# ORCA_Logic_Circuit_Pro.net
KiCad netlist of a schematic drawn in EasyEDA Pro
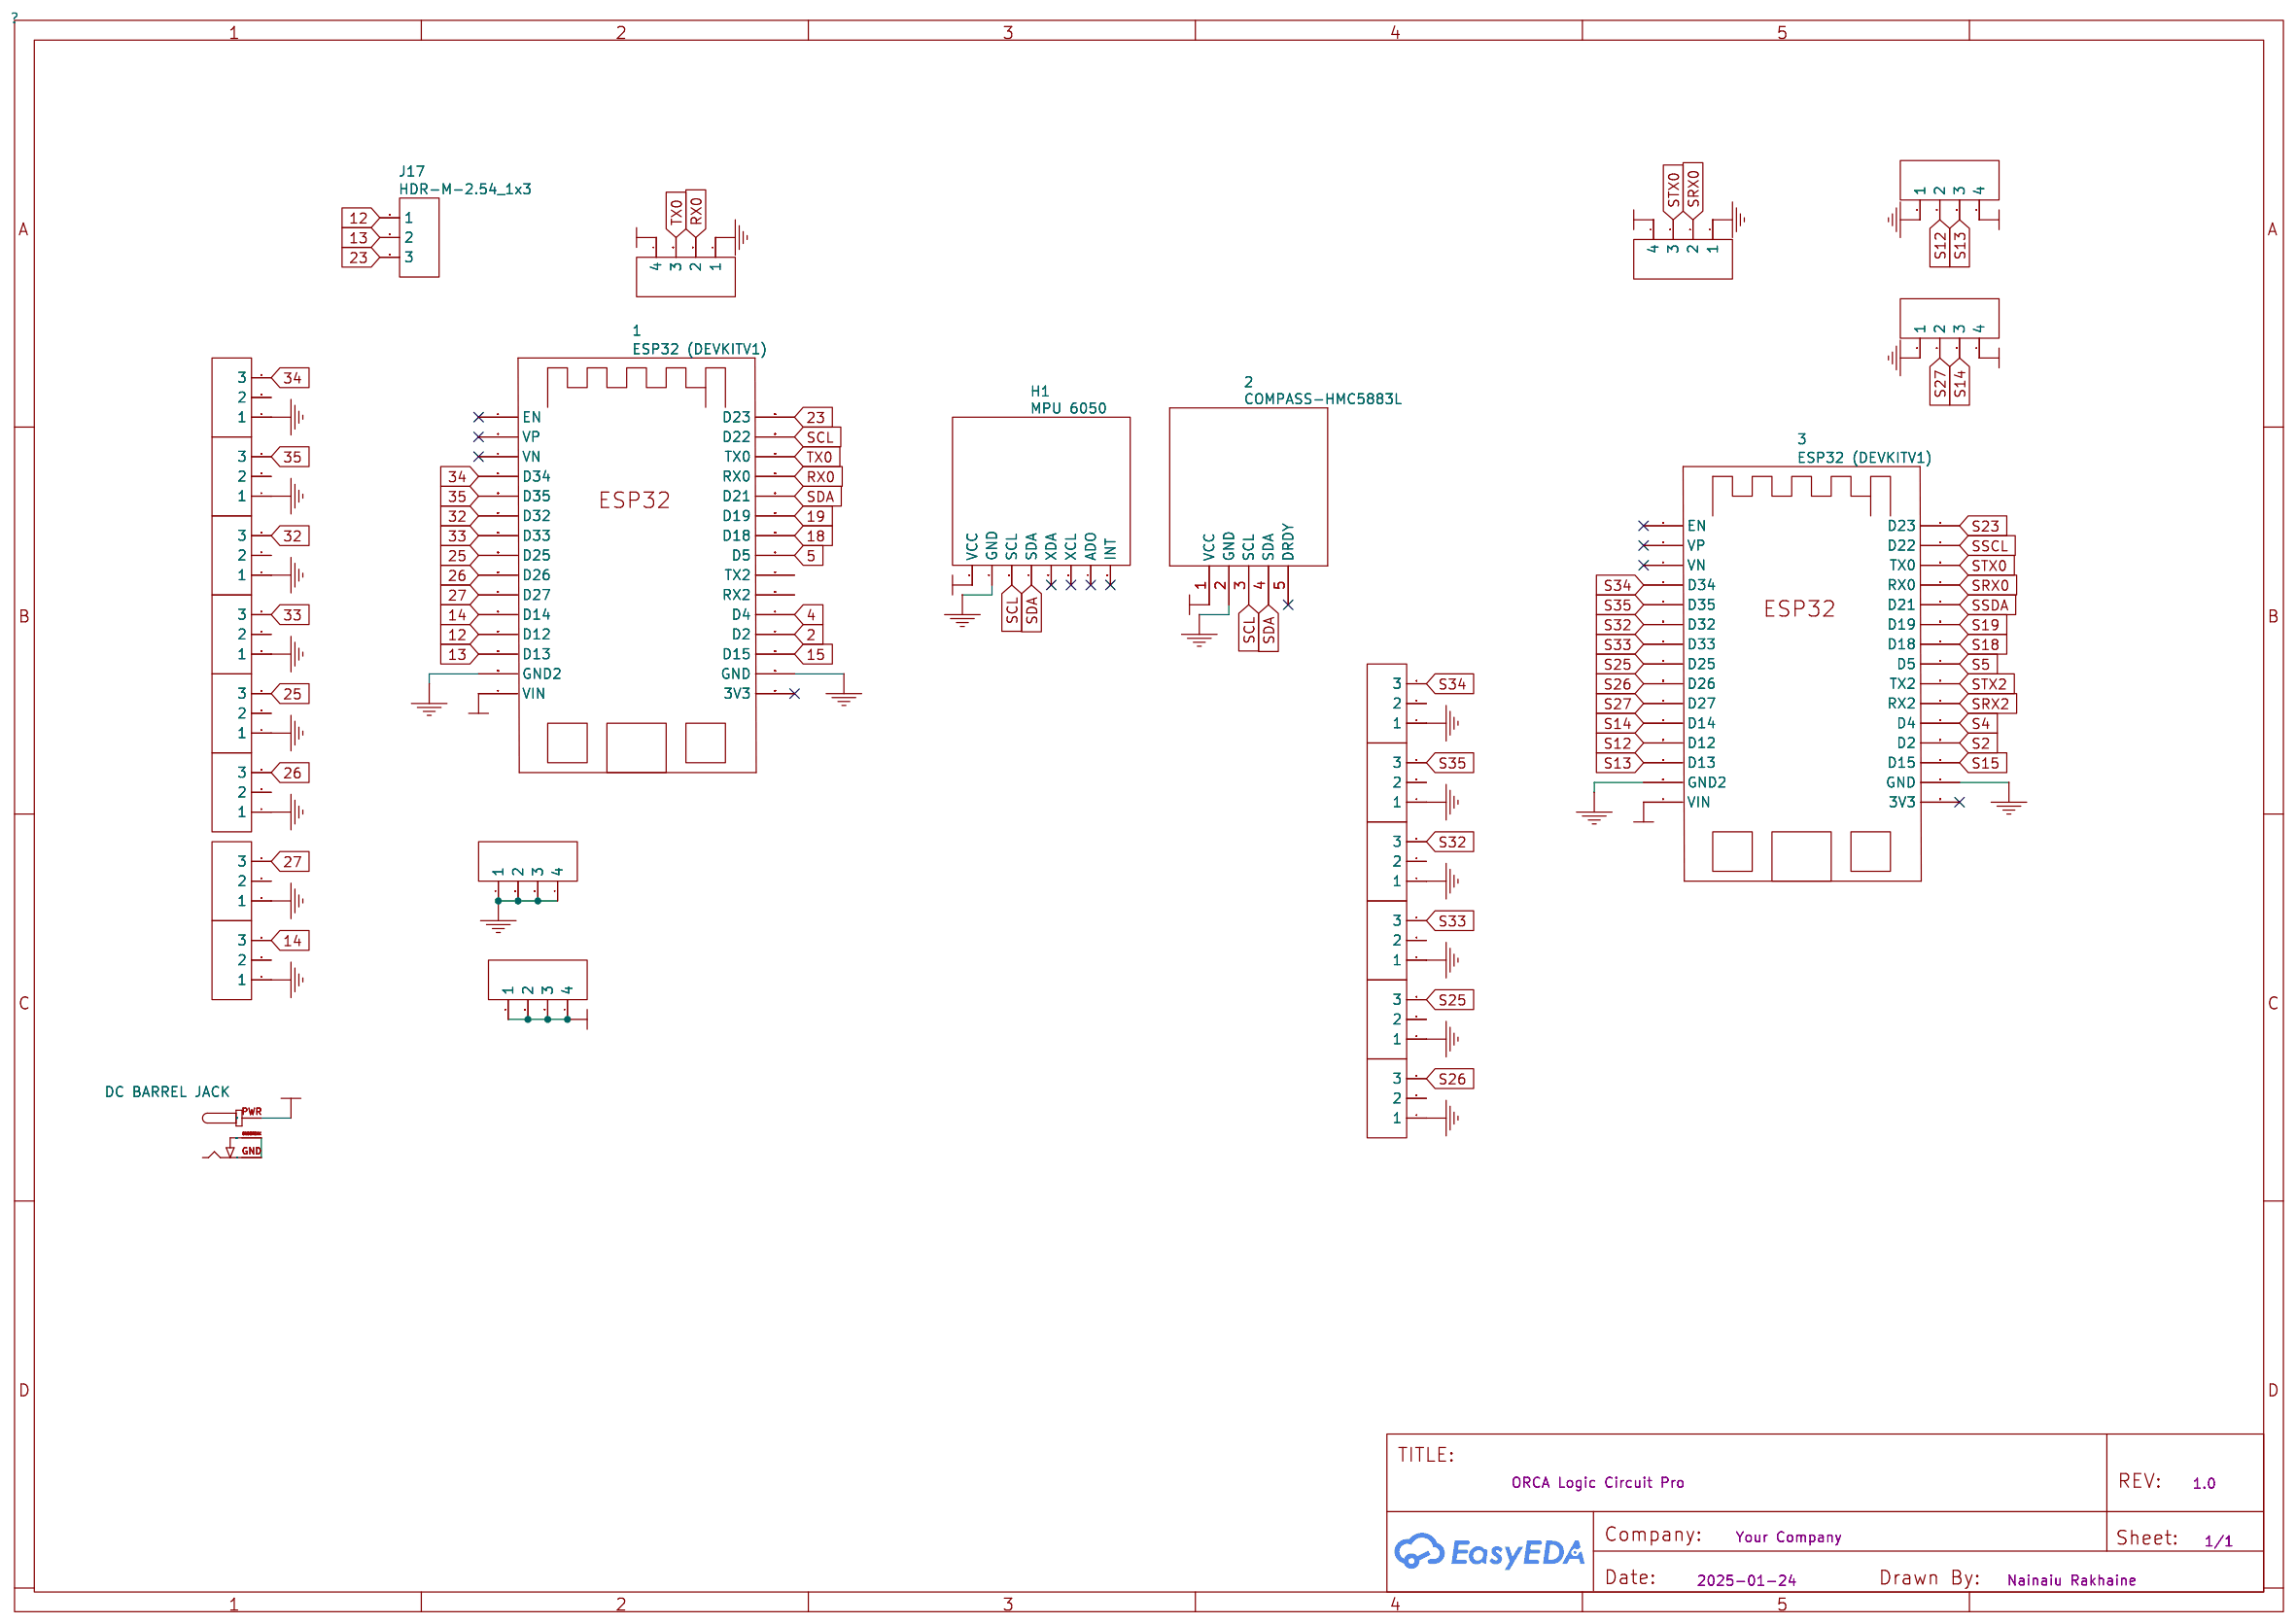
[diagram p0: schematic sheet]

(export (version "E")
  (design (tool "Eeschema 10.0.6"))
  (components
    (comp (ref "1")
      (value "ESP32 (DEVKITV1)")
      (footprint "easyedapro:ESP32-DEVKIT1")
      (libsource (lib "easyedapro") (part "ESP32 (DEVKITV1)"))
    )
    (comp (ref "2")
      (value "COMPASS-HMC5883L")
      (footprint "easyedapro:COMPASS-HMC5883L")
      (libsource (lib "easyedapro") (part "COMPASS-HMC5883L"))
    )
    (comp (ref "3")
      (value "ESP32 (DEVKITV1)")
      (footprint "easyedapro:ESP32-DEVKIT1")
      (libsource (lib "easyedapro") (part "ESP32 (DEVKITV1)"))
    )
    (comp (ref "H1")
      (value "MPU 6050")
      (footprint "easyedapro:MPU6050")
      (libsource (lib "easyedapro") (part "MPU 6050"))
    )
    (comp (ref "J1")
      (value "HDR-M-2.54_1x4")
      (footprint "easyedapro:HDR-M-2.54_1X4")
      (libsource (lib "easyedapro") (part "HDR-M-2.54_1x4"))
    )
    (comp (ref "J2")
      (value "HDR-M-2.54_1x4")
      (footprint "easyedapro:HDR-M-2.54_1X4")
      (libsource (lib "easyedapro") (part "HDR-M-2.54_1x4"))
    )
    (comp (ref "J3")
      (value "HDR-M-2.54_1x3")
      (footprint "easyedapro:HDR-M-2.54_1X3")
      (libsource (lib "") (part "HDR-M-2.54_1x3_1"))
    )
    (comp (ref "J4")
      (value "HDR-M-2.54_1x3")
      (footprint "easyedapro:HDR-M-2.54_1X3")
      (libsource (lib "") (part "HDR-M-2.54_1x3_1"))
    )
    (comp (ref "J5")
      (value "HDR-M-2.54_1x3")
      (footprint "easyedapro:HDR-M-2.54_1X3")
      (libsource (lib "") (part "HDR-M-2.54_1x3_1"))
    )
    (comp (ref "J6")
      (value "HDR-M-2.54_1x3")
      (footprint "easyedapro:HDR-M-2.54_1X3")
      (libsource (lib "") (part "HDR-M-2.54_1x3_1"))
    )
    (comp (ref "J7")
      (value "HDR-M-2.54_1x3")
      (footprint "easyedapro:HDR-M-2.54_1X3")
      (libsource (lib "") (part "HDR-M-2.54_1x3_1"))
    )
    (comp (ref "J8")
      (value "HDR-M-2.54_1x3")
      (footprint "easyedapro:HDR-M-2.54_1X3")
      (libsource (lib "") (part "HDR-M-2.54_1x3_1"))
    )
    (comp (ref "J9")
      (value "HDR-M-2.54_1x3")
      (footprint "easyedapro:HDR-M-2.54_1X3")
      (libsource (lib "") (part "HDR-M-2.54_1x3_1"))
    )
    (comp (ref "J10")
      (value "HDR-M-2.54_1x3")
      (footprint "easyedapro:HDR-M-2.54_1X3")
      (libsource (lib "") (part "HDR-M-2.54_1x3_1"))
    )
    (comp (ref "J11")
      (value "HDR-M-2.54_1x3")
      (footprint "easyedapro:HDR-M-2.54_1X3")
      (libsource (lib "") (part "HDR-M-2.54_1x3_1"))
    )
    (comp (ref "J12")
      (value "HDR-M-2.54_1x3")
      (footprint "easyedapro:HDR-M-2.54_1X3")
      (libsource (lib "") (part "HDR-M-2.54_1x3_1"))
    )
    (comp (ref "J13")
      (value "HDR-M-2.54_1x3")
      (footprint "easyedapro:HDR-M-2.54_1X3")
      (libsource (lib "") (part "HDR-M-2.54_1x3_1"))
    )
    (comp (ref "J14")
      (value "HDR-M-2.54_1x3")
      (footprint "easyedapro:HDR-M-2.54_1X3")
      (libsource (lib "") (part "HDR-M-2.54_1x3_1"))
    )
    (comp (ref "J15")
      (value "HDR-M-2.54_1x4")
      (footprint "easyedapro:HDR-M-2.54_1X4")
      (libsource (lib "easyedapro") (part "HDR-M-2.54_1x4"))
    )
    (comp (ref "J16")
      (value "HDR-M-2.54_1x4")
      (footprint "easyedapro:HDR-M-2.54_1X4")
      (libsource (lib "") (part "HDR-M-2.54_1x4_1"))
    )
    (comp (ref "J17")
      (value "HDR-M-2.54_1x3")
      (footprint "easyedapro:HDR-M-2.54_1X3")
      (libsource (lib "easyedapro") (part "HDR-M-2.54_1x3"))
    )
    (comp (ref "J18")
      (value "HDR-M-2.54_1x4")
      (footprint "easyedapro:HDR-M-2.54_1X4")
      (libsource (lib "") (part "HDR-M-2.54_1x4_1"))
    )
    (comp (ref "J19")
      (value "HDR-M-2.54_1x3")
      (footprint "easyedapro:HDR-M-2.54_1X3")
      (libsource (lib "") (part "HDR-M-2.54_1x3_1"))
    )
    (comp (ref "J21")
      (value "HDR-M-2.54_1x3")
      (footprint "easyedapro:HDR-M-2.54_1X3")
      (libsource (lib "") (part "HDR-M-2.54_1x3_1"))
    )
    (comp (ref "J22")
      (value "HDR-M-2.54_1x4")
      (footprint "easyedapro:HDR-M-2.54_1X4")
      (libsource (lib "easyedapro") (part "HDR-M-2.54_1x4"))
    )
    (comp (ref "U2")
      (value "DC BARREL JACK")
      (footprint "easyedapro:DCBARRELJACK")
      (libsource (lib "easyedapro") (part "DC BARREL JACK"))
    )
  )
  (nets
    (net (code "1") (name "+5V") (class "Default")
      (node (ref "1") (pin "VIN") (pinfunction "VIN_VIN") (pintype "unspecified"))
      (node (ref "2") (pin "1") (pinfunction "VCC_1") (pintype "bidirectional"))
      (node (ref "3") (pin "VIN") (pinfunction "VIN_VIN") (pintype "unspecified"))
      (node (ref "H1") (pin "1") (pinfunction "VCC_1") (pintype "unspecified"))
      (node (ref "J1") (pin "4") (pinfunction "4_4") (pintype "unspecified"))
      (node (ref "J15") (pin "1") (pinfunction "1_1") (pintype "unspecified"))
      (node (ref "J15") (pin "2") (pinfunction "2_2") (pintype "unspecified"))
      (node (ref "J15") (pin "3") (pinfunction "3_3") (pintype "unspecified"))
      (node (ref "J15") (pin "4") (pinfunction "4_4") (pintype "unspecified"))
      (node (ref "J16") (pin "4") (pinfunction "4_4") (pintype "unspecified"))
      (node (ref "J18") (pin "4") (pinfunction "4_4") (pintype "unspecified"))
      (node (ref "J22") (pin "4") (pinfunction "4_4") (pintype "unspecified"))
      (node (ref "U2") (pin "PWR") (pinfunction "PWR_PWR") (pintype "bidirectional"))
    )
    (net (code "2") (name "2") (class "Default")
      (node (ref "1") (pin "D2") (pinfunction "D2_D2") (pintype "unspecified"))
    )
    (net (code "3") (name "4") (class "Default")
      (node (ref "1") (pin "D4") (pinfunction "D4_D4") (pintype "unspecified"))
    )
    (net (code "4") (name "5") (class "Default")
      (node (ref "1") (pin "D5") (pinfunction "D5_D5") (pintype "unspecified"))
    )
    (net (code "5") (name "12") (class "Default")
      (node (ref "1") (pin "D12") (pinfunction "D12_D12") (pintype "unspecified"))
      (node (ref "J17") (pin "1") (pinfunction "1_1") (pintype "input"))
    )
    (net (code "6") (name "13") (class "Default")
      (node (ref "1") (pin "D13") (pinfunction "D13_D13") (pintype "unspecified"))
      (node (ref "J17") (pin "2") (pinfunction "2_2") (pintype "input"))
    )
    (net (code "7") (name "14") (class "Default")
      (node (ref "1") (pin "D14") (pinfunction "D14_D14") (pintype "unspecified"))
      (node (ref "J5") (pin "3") (pinfunction "3_3") (pintype "input"))
    )
    (net (code "8") (name "15") (class "Default")
      (node (ref "1") (pin "D15") (pinfunction "D15_D15") (pintype "unspecified"))
    )
    (net (code "9") (name "18") (class "Default")
      (node (ref "1") (pin "D18") (pinfunction "D18_D18") (pintype "unspecified"))
    )
    (net (code "10") (name "19") (class "Default")
      (node (ref "1") (pin "D19") (pinfunction "D19_D19") (pintype "unspecified"))
    )
    (net (code "11") (name "23") (class "Default")
      (node (ref "1") (pin "D23") (pinfunction "D23_D23") (pintype "unspecified"))
      (node (ref "J17") (pin "3") (pinfunction "3_3") (pintype "input"))
    )
    (net (code "12") (name "25") (class "Default")
      (node (ref "1") (pin "D25") (pinfunction "D25_D25") (pintype "unspecified"))
      (node (ref "J8") (pin "3") (pinfunction "3_3") (pintype "input"))
    )
    (net (code "13") (name "26") (class "Default")
      (node (ref "1") (pin "D26") (pinfunction "D26_D26") (pintype "unspecified"))
      (node (ref "J7") (pin "3") (pinfunction "3_3") (pintype "input"))
    )
    (net (code "14") (name "27") (class "Default")
      (node (ref "1") (pin "D27") (pinfunction "D27_D27") (pintype "unspecified"))
      (node (ref "J6") (pin "3") (pinfunction "3_3") (pintype "input"))
    )
    (net (code "15") (name "32") (class "Default")
      (node (ref "1") (pin "D32") (pinfunction "D32_D32") (pintype "unspecified"))
      (node (ref "J3") (pin "3") (pinfunction "3_3") (pintype "input"))
    )
    (net (code "16") (name "33") (class "Default")
      (node (ref "1") (pin "D33") (pinfunction "D33_D33") (pintype "unspecified"))
      (node (ref "J4") (pin "3") (pinfunction "3_3") (pintype "input"))
    )
    (net (code "17") (name "34") (class "Default")
      (node (ref "1") (pin "D34") (pinfunction "D34_D34") (pintype "unspecified"))
      (node (ref "J14") (pin "3") (pinfunction "3_3") (pintype "input"))
    )
    (net (code "18") (name "35") (class "Default")
      (node (ref "1") (pin "D35") (pinfunction "D35_D35") (pintype "unspecified"))
      (node (ref "J13") (pin "3") (pinfunction "3_3") (pintype "input"))
    )
    (net (code "19") (name "GND") (class "Default")
      (node (ref "1") (pin "GND") (pinfunction "GND_GND") (pintype "unspecified"))
      (node (ref "1") (pin "GND2") (pinfunction "GND2_GND2") (pintype "unspecified"))
      (node (ref "2") (pin "2") (pinfunction "GND_2") (pintype "bidirectional"))
      (node (ref "3") (pin "GND") (pinfunction "GND_GND") (pintype "unspecified"))
      (node (ref "3") (pin "GND2") (pinfunction "GND2_GND2") (pintype "unspecified"))
      (node (ref "H1") (pin "2") (pinfunction "GND_2") (pintype "unspecified"))
      (node (ref "J1") (pin "1") (pinfunction "1_1") (pintype "unspecified"))
      (node (ref "J10") (pin "1") (pinfunction "1_1") (pintype "input"))
      (node (ref "J11") (pin "1") (pinfunction "1_1") (pintype "input"))
      (node (ref "J12") (pin "1") (pinfunction "1_1") (pintype "input"))
      (node (ref "J13") (pin "1") (pinfunction "1_1") (pintype "input"))
      (node (ref "J14") (pin "1") (pinfunction "1_1") (pintype "input"))
      (node (ref "J16") (pin "1") (pinfunction "1_1") (pintype "unspecified"))
      (node (ref "J18") (pin "1") (pinfunction "1_1") (pintype "unspecified"))
      (node (ref "J19") (pin "1") (pinfunction "1_1") (pintype "input"))
      (node (ref "J2") (pin "1") (pinfunction "1_1") (pintype "unspecified"))
      (node (ref "J2") (pin "2") (pinfunction "2_2") (pintype "unspecified"))
      (node (ref "J2") (pin "3") (pinfunction "3_3") (pintype "unspecified"))
      (node (ref "J2") (pin "4") (pinfunction "4_4") (pintype "unspecified"))
      (node (ref "J21") (pin "1") (pinfunction "1_1") (pintype "input"))
      (node (ref "J22") (pin "1") (pinfunction "1_1") (pintype "unspecified"))
      (node (ref "J3") (pin "1") (pinfunction "1_1") (pintype "input"))
      (node (ref "J4") (pin "1") (pinfunction "1_1") (pintype "input"))
      (node (ref "J5") (pin "1") (pinfunction "1_1") (pintype "input"))
      (node (ref "J6") (pin "1") (pinfunction "1_1") (pintype "input"))
      (node (ref "J7") (pin "1") (pinfunction "1_1") (pintype "input"))
      (node (ref "J8") (pin "1") (pinfunction "1_1") (pintype "input"))
      (node (ref "J9") (pin "1") (pinfunction "1_1") (pintype "input"))
    )
    (net (code "20") (name "Net-(U2-PadGND)") (class "Default")
      (node (ref "U2") (pin "GND") (pinfunction "GND_GND") (pintype "bidirectional"))
      (node (ref "U2") (pin "GNDBREAK") (pinfunction "GNDBREAK_GNDBREAK") (pintype "bidirectional"))
    )
    (net (code "21") (name "RX0") (class "Default")
      (node (ref "1") (pin "RX0") (pinfunction "RX0_RX0") (pintype "unspecified"))
      (node (ref "J16") (pin "2") (pinfunction "2_2") (pintype "unspecified"))
    )
    (net (code "22") (name "S2") (class "Default")
      (node (ref "3") (pin "D2") (pinfunction "D2_D2") (pintype "unspecified"))
    )
    (net (code "23") (name "S4") (class "Default")
      (node (ref "3") (pin "D4") (pinfunction "D4_D4") (pintype "unspecified"))
    )
    (net (code "24") (name "S5") (class "Default")
      (node (ref "3") (pin "D5") (pinfunction "D5_D5") (pintype "unspecified"))
    )
    (net (code "25") (name "S12") (class "Default")
      (node (ref "3") (pin "D12") (pinfunction "D12_D12") (pintype "unspecified"))
      (node (ref "J1") (pin "2") (pinfunction "2_2") (pintype "unspecified"))
    )
    (net (code "26") (name "S13") (class "Default")
      (node (ref "3") (pin "D13") (pinfunction "D13_D13") (pintype "unspecified"))
      (node (ref "J1") (pin "3") (pinfunction "3_3") (pintype "unspecified"))
    )
    (net (code "27") (name "S14") (class "Default")
      (node (ref "3") (pin "D14") (pinfunction "D14_D14") (pintype "unspecified"))
      (node (ref "J22") (pin "3") (pinfunction "3_3") (pintype "unspecified"))
    )
    (net (code "28") (name "S15") (class "Default")
      (node (ref "3") (pin "D15") (pinfunction "D15_D15") (pintype "unspecified"))
    )
    (net (code "29") (name "S18") (class "Default")
      (node (ref "3") (pin "D18") (pinfunction "D18_D18") (pintype "unspecified"))
    )
    (net (code "30") (name "S19") (class "Default")
      (node (ref "3") (pin "D19") (pinfunction "D19_D19") (pintype "unspecified"))
    )
    (net (code "31") (name "S23") (class "Default")
      (node (ref "3") (pin "D23") (pinfunction "D23_D23") (pintype "unspecified"))
    )
    (net (code "32") (name "S25") (class "Default")
      (node (ref "3") (pin "D25") (pinfunction "D25_D25") (pintype "unspecified"))
      (node (ref "J19") (pin "3") (pinfunction "3_3") (pintype "input"))
    )
    (net (code "33") (name "S26") (class "Default")
      (node (ref "3") (pin "D26") (pinfunction "D26_D26") (pintype "unspecified"))
      (node (ref "J21") (pin "3") (pinfunction "3_3") (pintype "input"))
    )
    (net (code "34") (name "S27") (class "Default")
      (node (ref "3") (pin "D27") (pinfunction "D27_D27") (pintype "unspecified"))
      (node (ref "J22") (pin "2") (pinfunction "2_2") (pintype "unspecified"))
    )
    (net (code "35") (name "S32") (class "Default")
      (node (ref "3") (pin "D32") (pinfunction "D32_D32") (pintype "unspecified"))
      (node (ref "J11") (pin "3") (pinfunction "3_3") (pintype "input"))
    )
    (net (code "36") (name "S33") (class "Default")
      (node (ref "3") (pin "D33") (pinfunction "D33_D33") (pintype "unspecified"))
      (node (ref "J12") (pin "3") (pinfunction "3_3") (pintype "input"))
    )
    (net (code "37") (name "S34") (class "Default")
      (node (ref "3") (pin "D34") (pinfunction "D34_D34") (pintype "unspecified"))
      (node (ref "J9") (pin "3") (pinfunction "3_3") (pintype "input"))
    )
    (net (code "38") (name "S35") (class "Default")
      (node (ref "3") (pin "D35") (pinfunction "D35_D35") (pintype "unspecified"))
      (node (ref "J10") (pin "3") (pinfunction "3_3") (pintype "input"))
    )
    (net (code "39") (name "SCL") (class "Default")
      (node (ref "1") (pin "D22") (pinfunction "D22_D22") (pintype "unspecified"))
      (node (ref "2") (pin "3") (pinfunction "SCL_3") (pintype "bidirectional"))
      (node (ref "H1") (pin "3") (pinfunction "SCL_3") (pintype "unspecified"))
    )
    (net (code "40") (name "SDA") (class "Default")
      (node (ref "1") (pin "D21") (pinfunction "D21_D21") (pintype "unspecified"))
      (node (ref "2") (pin "4") (pinfunction "SDA_4") (pintype "bidirectional"))
      (node (ref "H1") (pin "4") (pinfunction "SDA_4") (pintype "unspecified"))
    )
    (net (code "41") (name "SRX0") (class "Default")
      (node (ref "3") (pin "RX0") (pinfunction "RX0_RX0") (pintype "unspecified"))
      (node (ref "J18") (pin "2") (pinfunction "2_2") (pintype "unspecified"))
    )
    (net (code "42") (name "SRX2") (class "Default")
      (node (ref "3") (pin "RX2") (pinfunction "RX2_RX2") (pintype "unspecified"))
    )
    (net (code "43") (name "SSCL") (class "Default")
      (node (ref "3") (pin "D22") (pinfunction "D22_D22") (pintype "unspecified"))
    )
    (net (code "44") (name "SSDA") (class "Default")
      (node (ref "3") (pin "D21") (pinfunction "D21_D21") (pintype "unspecified"))
    )
    (net (code "45") (name "STX0") (class "Default")
      (node (ref "3") (pin "TX0") (pinfunction "TX0_TX0") (pintype "unspecified"))
      (node (ref "J18") (pin "3") (pinfunction "3_3") (pintype "unspecified"))
    )
    (net (code "46") (name "STX2") (class "Default")
      (node (ref "3") (pin "TX2") (pinfunction "TX2_TX2") (pintype "unspecified"))
    )
    (net (code "47") (name "TX0") (class "Default")
      (node (ref "1") (pin "TX0") (pinfunction "TX0_TX0") (pintype "unspecified"))
      (node (ref "J16") (pin "3") (pinfunction "3_3") (pintype "unspecified"))
    )
    (net (code "48") (name "unconnected-(1-Pad3V3)") (class "Default")
      (node (ref "1") (pin "3V3") (pinfunction "3V3_3V3") (pintype "unspecified+no_connect"))
    )
    (net (code "49") (name "unconnected-(1-PadEN)") (class "Default")
      (node (ref "1") (pin "EN") (pinfunction "EN_EN") (pintype "unspecified+no_connect"))
    )
    (net (code "50") (name "unconnected-(1-PadRX2)") (class "Default")
      (node (ref "1") (pin "RX2") (pinfunction "RX2_RX2") (pintype "unspecified"))
    )
    (net (code "51") (name "unconnected-(1-PadTX2)") (class "Default")
      (node (ref "1") (pin "TX2") (pinfunction "TX2_TX2") (pintype "unspecified"))
    )
    (net (code "52") (name "unconnected-(1-PadVN)") (class "Default")
      (node (ref "1") (pin "VN") (pinfunction "VN_VN") (pintype "unspecified+no_connect"))
    )
    (net (code "53") (name "unconnected-(1-PadVP)") (class "Default")
      (node (ref "1") (pin "VP") (pinfunction "VP_VP") (pintype "unspecified+no_connect"))
    )
    (net (code "54") (name "unconnected-(2-DRDY-Pad5)") (class "Default")
      (node (ref "2") (pin "5") (pinfunction "DRDY_5") (pintype "bidirectional+no_connect"))
    )
    (net (code "55") (name "unconnected-(3-Pad3V3)") (class "Default")
      (node (ref "3") (pin "3V3") (pinfunction "3V3_3V3") (pintype "unspecified+no_connect"))
    )
    (net (code "56") (name "unconnected-(3-PadEN)") (class "Default")
      (node (ref "3") (pin "EN") (pinfunction "EN_EN") (pintype "unspecified+no_connect"))
    )
    (net (code "57") (name "unconnected-(3-PadVN)") (class "Default")
      (node (ref "3") (pin "VN") (pinfunction "VN_VN") (pintype "unspecified+no_connect"))
    )
    (net (code "58") (name "unconnected-(3-PadVP)") (class "Default")
      (node (ref "3") (pin "VP") (pinfunction "VP_VP") (pintype "unspecified+no_connect"))
    )
    (net (code "59") (name "unconnected-(H1-ADO-Pad7)") (class "Default")
      (node (ref "H1") (pin "7") (pinfunction "ADO_7") (pintype "unspecified+no_connect"))
    )
    (net (code "60") (name "unconnected-(H1-INT-Pad8)") (class "Default")
      (node (ref "H1") (pin "8") (pinfunction "INT_8") (pintype "unspecified+no_connect"))
    )
    (net (code "61") (name "unconnected-(H1-XCL-Pad6)") (class "Default")
      (node (ref "H1") (pin "6") (pinfunction "XCL_6") (pintype "unspecified+no_connect"))
    )
    (net (code "62") (name "unconnected-(H1-XDA-Pad5)") (class "Default")
      (node (ref "H1") (pin "5") (pinfunction "XDA_5") (pintype "unspecified+no_connect"))
    )
    (net (code "63") (name "unconnected-(J3-Pad2)") (class "Default")
      (node (ref "J3") (pin "2") (pinfunction "2_2") (pintype "input"))
    )
    (net (code "64") (name "unconnected-(J4-Pad2)") (class "Default")
      (node (ref "J4") (pin "2") (pinfunction "2_2") (pintype "input"))
    )
    (net (code "65") (name "unconnected-(J5-Pad2)") (class "Default")
      (node (ref "J5") (pin "2") (pinfunction "2_2") (pintype "input"))
    )
    (net (code "66") (name "unconnected-(J6-Pad2)") (class "Default")
      (node (ref "J6") (pin "2") (pinfunction "2_2") (pintype "input"))
    )
    (net (code "67") (name "unconnected-(J7-Pad2)") (class "Default")
      (node (ref "J7") (pin "2") (pinfunction "2_2") (pintype "input"))
    )
    (net (code "68") (name "unconnected-(J8-Pad2)") (class "Default")
      (node (ref "J8") (pin "2") (pinfunction "2_2") (pintype "input"))
    )
    (net (code "69") (name "unconnected-(J9-Pad2)") (class "Default")
      (node (ref "J9") (pin "2") (pinfunction "2_2") (pintype "input"))
    )
    (net (code "70") (name "unconnected-(J10-Pad2)") (class "Default")
      (node (ref "J10") (pin "2") (pinfunction "2_2") (pintype "input"))
    )
    (net (code "71") (name "unconnected-(J11-Pad2)") (class "Default")
      (node (ref "J11") (pin "2") (pinfunction "2_2") (pintype "input"))
    )
    (net (code "72") (name "unconnected-(J12-Pad2)") (class "Default")
      (node (ref "J12") (pin "2") (pinfunction "2_2") (pintype "input"))
    )
    (net (code "73") (name "unconnected-(J13-Pad2)") (class "Default")
      (node (ref "J13") (pin "2") (pinfunction "2_2") (pintype "input"))
    )
    (net (code "74") (name "unconnected-(J14-Pad2)") (class "Default")
      (node (ref "J14") (pin "2") (pinfunction "2_2") (pintype "input"))
    )
    (net (code "75") (name "unconnected-(J19-Pad2)") (class "Default")
      (node (ref "J19") (pin "2") (pinfunction "2_2") (pintype "input"))
    )
    (net (code "76") (name "unconnected-(J21-Pad2)") (class "Default")
      (node (ref "J21") (pin "2") (pinfunction "2_2") (pintype "input"))
    )
  )
)
